# Hammerhead_-_USB_R1_1.net
KiCad netlist of a schematic drawn in Altium Designer
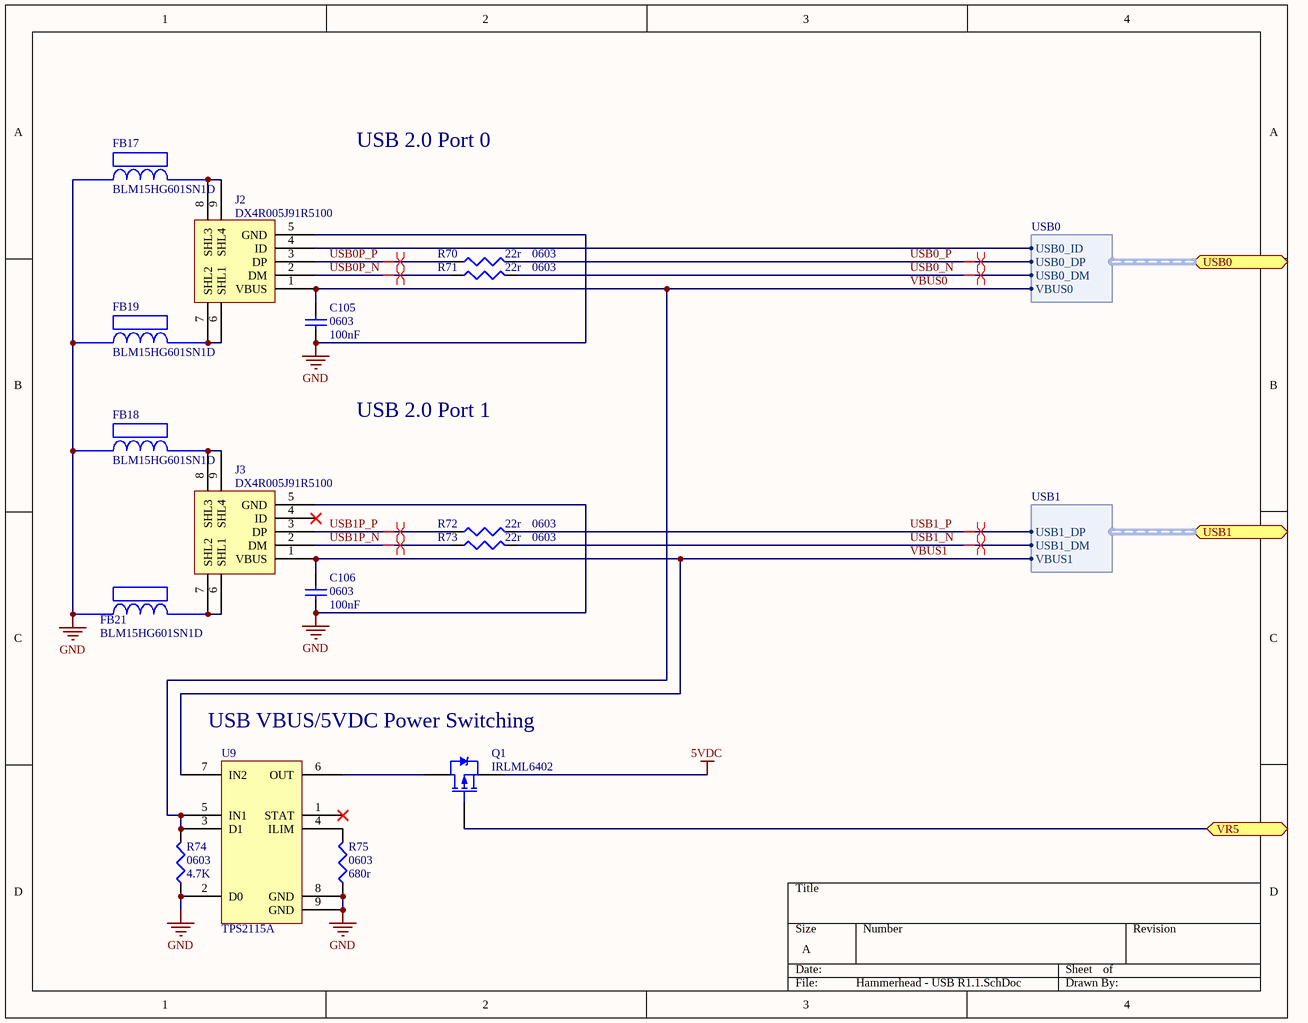
[diagram p0: Hammerhead - USB R1.1.SchDoc]

(export (version "E")
  (design (tool "Eeschema 10.0.6"))
  (components
    (comp (ref "C105")
      (value "0603")
      (footprint "1608[0603]")
      (description "Capacitor (Semiconductor SIM Model)")
      (fields (field (name "ALTIUM_VALUE") "100nF") (field (name "PUBLISHER") "Altium Limited"))
      (libsource (lib "Miscellaneous Devices") (part "Cap Semi"))
    )
    (comp (ref "C106")
      (value "0603")
      (footprint "1608[0603]")
      (description "Capacitor (Semiconductor SIM Model)")
      (fields (field (name "ALTIUM_VALUE") "100nF") (field (name "PUBLISHER") "Altium Limited"))
      (libsource (lib "Miscellaneous Devices") (part "Cap Semi"))
    )
    (comp (ref "FB17")
      (value "BLM15HG601SN1D")
      (footprint "BLM18PG121SN1D")
      (libsource (lib "Adams Altium Library") (part "BLM15HG601SN1D"))
    )
    (comp (ref "FB18")
      (value "BLM15HG601SN1D")
      (footprint "BLM18PG121SN1D")
      (libsource (lib "Adams Altium Library") (part "BLM15HG601SN1D"))
    )
    (comp (ref "FB19")
      (value "BLM15HG601SN1D")
      (footprint "BLM18PG121SN1D")
      (libsource (lib "Adams Altium Library") (part "BLM15HG601SN1D"))
    )
    (comp (ref "FB21")
      (value "BLM15HG601SN1D")
      (footprint "BLM18PG121SN1D")
      (libsource (lib "Adams Altium Library") (part "BLM15HG601SN1D"))
    )
    (comp (ref "J2")
      (value "DX4R005J91R5100")
      (footprint "Micro USB Circular Holes Only")
      (description "Micro USB Jack B")
      (libsource (lib "") (part "Micro USB_1"))
    )
    (comp (ref "J3")
      (value "DX4R005J91R5100")
      (footprint "Micro USB Circular Holes Only")
      (description "Micro USB Jack B")
      (libsource (lib "SunIO Schematic Symbol Lib") (part "Micro USB"))
    )
    (comp (ref "Q1")
      (value "IRLML6402")
      (footprint "SOT95P237X112-3N")
      (description "P-Channel Power MOSFET")
      (fields (field (name "PUBLISHER") "Altium Limited"))
      (libsource (lib "Miscellaneous Devices") (part "PMOS-2"))
    )
    (comp (ref "R70")
      (value "0603")
      (footprint "J1-0603")
      (description "Resistor")
      (fields (field (name "ALTIUM_VALUE") "22r") (field (name "PUBLISHER") "Altium Limited"))
      (libsource (lib "Miscellaneous Devices") (part "Res3"))
    )
    (comp (ref "R71")
      (value "0603")
      (footprint "J1-0603")
      (description "Resistor")
      (fields (field (name "ALTIUM_VALUE") "22r") (field (name "PUBLISHER") "Altium Limited"))
      (libsource (lib "Miscellaneous Devices") (part "Res3"))
    )
    (comp (ref "R72")
      (value "0603")
      (footprint "J1-0603")
      (description "Resistor")
      (fields (field (name "ALTIUM_VALUE") "22r") (field (name "PUBLISHER") "Altium Limited"))
      (libsource (lib "Miscellaneous Devices") (part "Res3"))
    )
    (comp (ref "R73")
      (value "0603")
      (footprint "J1-0603")
      (description "Resistor")
      (fields (field (name "ALTIUM_VALUE") "22r") (field (name "PUBLISHER") "Altium Limited"))
      (libsource (lib "Miscellaneous Devices") (part "Res3"))
    )
    (comp (ref "R74")
      (value "0603")
      (footprint "J1-0603")
      (description "Resistor")
      (fields (field (name "ALTIUM_VALUE") "4.7K") (field (name "PUBLISHER") "Altium Limited"))
      (libsource (lib "Miscellaneous Devices") (part "Res3"))
    )
    (comp (ref "R75")
      (value "0603")
      (footprint "J1-0603")
      (description "Resistor")
      (fields (field (name "ALTIUM_VALUE") "680r") (field (name "PUBLISHER") "Altium Limited"))
      (libsource (lib "Miscellaneous Devices") (part "Res3"))
    )
    (comp (ref "U9")
      (value "TPS2115A")
      (footprint "DRB S-PVSON-N8")
      (libsource (lib "SunIO Schematic Symbol Lib") (part "TPS2115A"))
    )
  )
  (nets
    (net (code "3") (name "/USB0P_N") (class "Default")
      (node (ref "J2") (pin "2") (pinfunction "DM_2") (pintype "passive"))
      (node (ref "R71") (pin "1") (pinfunction "1_1") (pintype "passive"))
    )
    (net (code "4") (name "/USB0P_P") (class "Default")
      (node (ref "J2") (pin "3") (pinfunction "DP_3") (pintype "passive"))
      (node (ref "R70") (pin "1") (pinfunction "1_1") (pintype "passive"))
    )
    (net (code "5") (name "/USB0_ID") (class "Default")
      (node (ref "J2") (pin "4") (pinfunction "ID_4") (pintype "passive"))
    )
    (net (code "6") (name "/USB0_N") (class "Default")
      (node (ref "R71") (pin "2") (pinfunction "2_2") (pintype "passive"))
    )
    (net (code "7") (name "/USB0_P") (class "Default")
      (node (ref "R70") (pin "2") (pinfunction "2_2") (pintype "passive"))
    )
    (net (code "8") (name "/USB1P_N") (class "Default")
      (node (ref "J3") (pin "2") (pinfunction "DM_2") (pintype "passive"))
      (node (ref "R73") (pin "1") (pinfunction "1_1") (pintype "passive"))
    )
    (net (code "9") (name "/USB1P_P") (class "Default")
      (node (ref "J3") (pin "3") (pinfunction "DP_3") (pintype "passive"))
      (node (ref "R72") (pin "1") (pinfunction "1_1") (pintype "passive"))
    )
    (net (code "10") (name "/USB1_N") (class "Default")
      (node (ref "R73") (pin "2") (pinfunction "2_2") (pintype "passive"))
    )
    (net (code "11") (name "/USB1_P") (class "Default")
      (node (ref "R72") (pin "2") (pinfunction "2_2") (pintype "passive"))
    )
    (net (code "12") (name "/VBUS0") (class "Default")
      (node (ref "C105") (pin "2") (pinfunction "2_2") (pintype "passive"))
      (node (ref "J2") (pin "1") (pinfunction "VBUS_1") (pintype "passive"))
      (node (ref "R74") (pin "2") (pinfunction "2_2") (pintype "passive"))
      (node (ref "U9") (pin "3") (pinfunction "D1_3") (pintype "passive"))
      (node (ref "U9") (pin "5") (pinfunction "IN1_5") (pintype "passive"))
    )
    (net (code "13") (name "/VBUS1") (class "Default")
      (node (ref "C106") (pin "2") (pinfunction "2_2") (pintype "passive"))
      (node (ref "J3") (pin "1") (pinfunction "VBUS_1") (pintype "passive"))
      (node (ref "U9") (pin "7") (pinfunction "IN2_7") (pintype "passive"))
    )
    (net (code "14") (name "/VR5") (class "Default")
      (node (ref "Q1") (pin "1") (pinfunction "G_1") (pintype "passive"))
    )
    (net (code "17") (name "5VDC") (class "Default")
      (node (ref "Q1") (pin "3") (pinfunction "S_3") (pintype "passive"))
    )
    (net (code "18") (name "GND") (class "Default")
      (node (ref "C105") (pin "1") (pinfunction "1_1") (pintype "passive"))
      (node (ref "C106") (pin "1") (pinfunction "1_1") (pintype "passive"))
      (node (ref "FB17") (pin "1") (pinfunction "1_1") (pintype "passive"))
      (node (ref "FB18") (pin "1") (pinfunction "1_1") (pintype "passive"))
      (node (ref "FB19") (pin "1") (pinfunction "1_1") (pintype "passive"))
      (node (ref "FB21") (pin "1") (pinfunction "1_1") (pintype "passive"))
      (node (ref "J2") (pin "5") (pinfunction "GND_5") (pintype "passive"))
      (node (ref "J3") (pin "5") (pinfunction "GND_5") (pintype "passive"))
      (node (ref "R74") (pin "1") (pinfunction "1_1") (pintype "passive"))
      (node (ref "R75") (pin "1") (pinfunction "1_1") (pintype "passive"))
      (node (ref "U9") (pin "2") (pinfunction "D0_2") (pintype "passive"))
      (node (ref "U9") (pin "8") (pinfunction "GND_8") (pintype "passive"))
      (node (ref "U9") (pin "9") (pinfunction "GND_9") (pintype "passive"))
    )
    (net (code "19") (name "Net-(J2-SHL1)") (class "Default")
      (node (ref "FB19") (pin "2") (pinfunction "2_2") (pintype "passive"))
      (node (ref "J2") (pin "6") (pinfunction "SHL1_6") (pintype "passive"))
      (node (ref "J2") (pin "7") (pinfunction "SHL2_7") (pintype "passive"))
    )
    (net (code "20") (name "Net-(J2-SHL3)") (class "Default")
      (node (ref "FB17") (pin "2") (pinfunction "2_2") (pintype "passive"))
      (node (ref "J2") (pin "8") (pinfunction "SHL3_8") (pintype "passive"))
      (node (ref "J2") (pin "9") (pinfunction "SHL4_9") (pintype "passive"))
    )
    (net (code "21") (name "Net-(J3-SHL1)") (class "Default")
      (node (ref "FB21") (pin "2") (pinfunction "2_2") (pintype "passive"))
      (node (ref "J3") (pin "6") (pinfunction "SHL1_6") (pintype "passive"))
      (node (ref "J3") (pin "7") (pinfunction "SHL2_7") (pintype "passive"))
    )
    (net (code "22") (name "Net-(J3-SHL3)") (class "Default")
      (node (ref "FB18") (pin "2") (pinfunction "2_2") (pintype "passive"))
      (node (ref "J3") (pin "8") (pinfunction "SHL3_8") (pintype "passive"))
      (node (ref "J3") (pin "9") (pinfunction "SHL4_9") (pintype "passive"))
    )
    (net (code "23") (name "Net-(Q1-D)") (class "Default")
      (node (ref "Q1") (pin "2") (pinfunction "D_2") (pintype "passive"))
      (node (ref "U9") (pin "6") (pinfunction "OUT_6") (pintype "passive"))
    )
    (net (code "24") (name "Net-(U9-ILIM)") (class "Default")
      (node (ref "R75") (pin "2") (pinfunction "2_2") (pintype "passive"))
      (node (ref "U9") (pin "4") (pinfunction "ILIM_4") (pintype "passive"))
    )
    (net (code "25") (name "unconnected-(J3-ID-Pad4)") (class "Default")
      (node (ref "J3") (pin "4") (pinfunction "ID_4") (pintype "passive+no_connect"))
    )
    (net (code "26") (name "unconnected-(U9-STAT-Pad1)") (class "Default")
      (node (ref "U9") (pin "1") (pinfunction "STAT_1") (pintype "passive+no_connect"))
    )
  )
)
